# motor_driver.net
KiCad netlist of a schematic drawn in Altium Designer
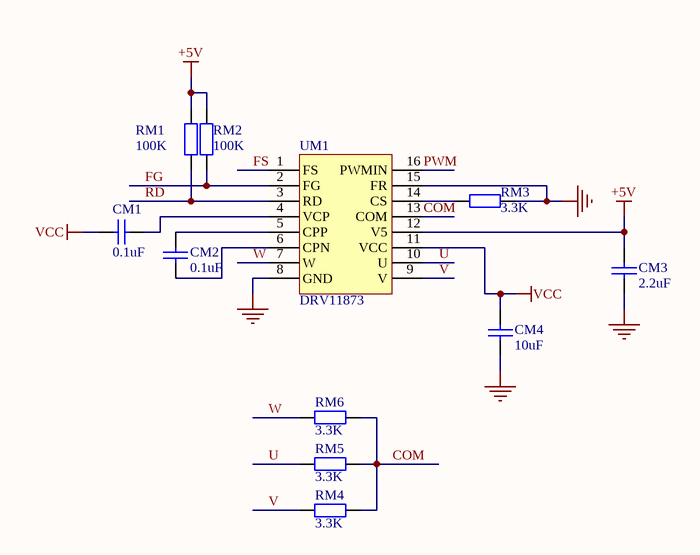
[diagram p0: motor_driver.SchDoc]

(export (version "E")
  (design (tool "Eeschema 10.0.6"))
  (components
    (comp (ref "CM1")
      (value "0.1uF")
      (footprint "CAPC1608N")
      (description "Capacitor")
      (fields (field (name "Comment") "Cap1") (field (name "PUBLISHER") "Altium Limited"))
      (libsource (lib "Peace的集成库") (part "Cap1"))
    )
    (comp (ref "CM2")
      (value "0.1uF")
      (footprint "CAPC1608N")
      (description "Capacitor")
      (fields (field (name "Comment") "Cap1") (field (name "PUBLISHER") "Altium Limited"))
      (libsource (lib "Peace的集成库") (part "Cap1"))
    )
    (comp (ref "CM3")
      (value "2.2uF")
      (footprint "CAPC1608N")
      (description "Capacitor")
      (fields (field (name "Comment") "Cap1") (field (name "PUBLISHER") "Altium Limited"))
      (libsource (lib "Peace的集成库") (part "Cap1"))
    )
    (comp (ref "CM4")
      (value "10uF")
      (footprint "CAPC1608N")
      (description "Capacitor")
      (fields (field (name "Comment") "Cap1") (field (name "PUBLISHER") "Altium Limited"))
      (libsource (lib "Peace的集成库") (part "Cap1"))
    )
    (comp (ref "RM1")
      (value "100K")
      (footprint "RESC1608N")
      (description "Resistor")
      (fields (field (name "Comment") "Res1") (field (name "PUBLISHER") "Altium Limited"))
      (libsource (lib "Peace的集成库") (part "Res1"))
    )
    (comp (ref "RM2")
      (value "100K")
      (footprint "RESC1608N")
      (description "Resistor")
      (fields (field (name "Comment") "Res1") (field (name "PUBLISHER") "Altium Limited"))
      (libsource (lib "Peace的集成库") (part "Res1"))
    )
    (comp (ref "RM3")
      (value "3.3K")
      (footprint "RESC1608N")
      (description "Resistor")
      (fields (field (name "Comment") "Res1") (field (name "PUBLISHER") "Altium Limited"))
      (libsource (lib "") (part "Res1_2"))
    )
    (comp (ref "RM4")
      (value "3.3K")
      (footprint "RESC1608N")
      (description "Resistor")
      (fields (field (name "Comment") "Res1") (field (name "PUBLISHER") "Altium Limited"))
      (libsource (lib "") (part "Res1_1"))
    )
    (comp (ref "RM5")
      (value "3.3K")
      (footprint "RESC1608N")
      (description "Resistor")
      (fields (field (name "Comment") "Res1") (field (name "PUBLISHER") "Altium Limited"))
      (libsource (lib "") (part "Res1_1"))
    )
    (comp (ref "RM6")
      (value "3.3K")
      (footprint "RESC1608N")
      (description "Resistor")
      (fields (field (name "Comment") "Res1") (field (name "PUBLISHER") "Altium Limited"))
      (libsource (lib "") (part "Res1_1"))
    )
    (comp (ref "UM1")
      (value "DRV11873")
      (footprint "TSSOP-16N")
      (description "三相无传感器、 无刷直流 (BLDC) 电机驱动器")
      (libsource (lib "Peace的集成库") (part "DRV11873"))
    )
  )
  (nets
    (net (code "1") (name "+5V") (class "Default")
      (node (ref "CM3") (pin "1") (pinfunction "1_1") (pintype "passive"))
      (node (ref "RM1") (pin "2") (pinfunction "2_2") (pintype "passive"))
      (node (ref "RM2") (pin "2") (pinfunction "2_2") (pintype "passive"))
      (node (ref "UM1") (pin "12") (pinfunction "V5_12") (pintype "passive"))
    )
    (net (code "2") (name "/COM") (class "Default")
      (node (ref "RM4") (pin "2") (pinfunction "2_2") (pintype "passive"))
      (node (ref "RM5") (pin "2") (pinfunction "2_2") (pintype "passive"))
      (node (ref "RM6") (pin "2") (pinfunction "2_2") (pintype "passive"))
      (node (ref "UM1") (pin "13") (pinfunction "COM_13") (pintype "passive"))
    )
    (net (code "3") (name "/FG") (class "Default")
      (node (ref "RM2") (pin "1") (pinfunction "1_1") (pintype "passive"))
      (node (ref "UM1") (pin "2") (pinfunction "FG_2") (pintype "passive"))
    )
    (net (code "4") (name "/FS") (class "Default")
      (node (ref "UM1") (pin "1") (pinfunction "FS_1") (pintype "passive"))
    )
    (net (code "5") (name "/PWM") (class "Default")
      (node (ref "UM1") (pin "16") (pinfunction "PWMIN_16") (pintype "passive"))
    )
    (net (code "6") (name "/RD") (class "Default")
      (node (ref "RM1") (pin "1") (pinfunction "1_1") (pintype "passive"))
      (node (ref "UM1") (pin "3") (pinfunction "RD_3") (pintype "passive"))
    )
    (net (code "7") (name "/U") (class "Default")
      (node (ref "RM5") (pin "1") (pinfunction "1_1") (pintype "passive"))
      (node (ref "UM1") (pin "10") (pinfunction "U_10") (pintype "passive"))
    )
    (net (code "8") (name "/V") (class "Default")
      (node (ref "RM4") (pin "1") (pinfunction "1_1") (pintype "passive"))
      (node (ref "UM1") (pin "9") (pinfunction "V_9") (pintype "passive"))
    )
    (net (code "9") (name "/W") (class "Default")
      (node (ref "RM6") (pin "1") (pinfunction "1_1") (pintype "passive"))
      (node (ref "UM1") (pin "7") (pinfunction "W_7") (pintype "passive"))
    )
    (net (code "10") (name "GND") (class "Default")
      (node (ref "CM3") (pin "2") (pinfunction "2_2") (pintype "passive"))
      (node (ref "CM4") (pin "2") (pinfunction "2_2") (pintype "passive"))
      (node (ref "RM3") (pin "1") (pinfunction "1_1") (pintype "passive"))
      (node (ref "UM1") (pin "15") (pinfunction "FR_15") (pintype "passive"))
      (node (ref "UM1") (pin "8") (pinfunction "GND_8") (pintype "passive"))
    )
    (net (code "11") (name "Net-(UM1-CPN)") (class "Default")
      (node (ref "CM2") (pin "2") (pinfunction "2_2") (pintype "passive"))
      (node (ref "UM1") (pin "6") (pinfunction "CPN_6") (pintype "passive"))
    )
    (net (code "12") (name "Net-(UM1-CPP)") (class "Default")
      (node (ref "CM2") (pin "1") (pinfunction "1_1") (pintype "passive"))
      (node (ref "UM1") (pin "5") (pinfunction "CPP_5") (pintype "passive"))
    )
    (net (code "13") (name "Net-(UM1-CS)") (class "Default")
      (node (ref "RM3") (pin "2") (pinfunction "2_2") (pintype "passive"))
      (node (ref "UM1") (pin "14") (pinfunction "CS_14") (pintype "passive"))
    )
    (net (code "14") (name "Net-(UM1-VCP)") (class "Default")
      (node (ref "CM1") (pin "1") (pinfunction "1_1") (pintype "passive"))
      (node (ref "UM1") (pin "4") (pinfunction "VCP_4") (pintype "passive"))
    )
    (net (code "15") (name "VCC") (class "Default")
      (node (ref "CM1") (pin "2") (pinfunction "2_2") (pintype "passive"))
      (node (ref "CM4") (pin "1") (pinfunction "1_1") (pintype "passive"))
      (node (ref "UM1") (pin "11") (pinfunction "VCC_11") (pintype "passive"))
    )
  )
)
